# ET-TOP.net
KiCad netlist of a schematic drawn in Altium Designer
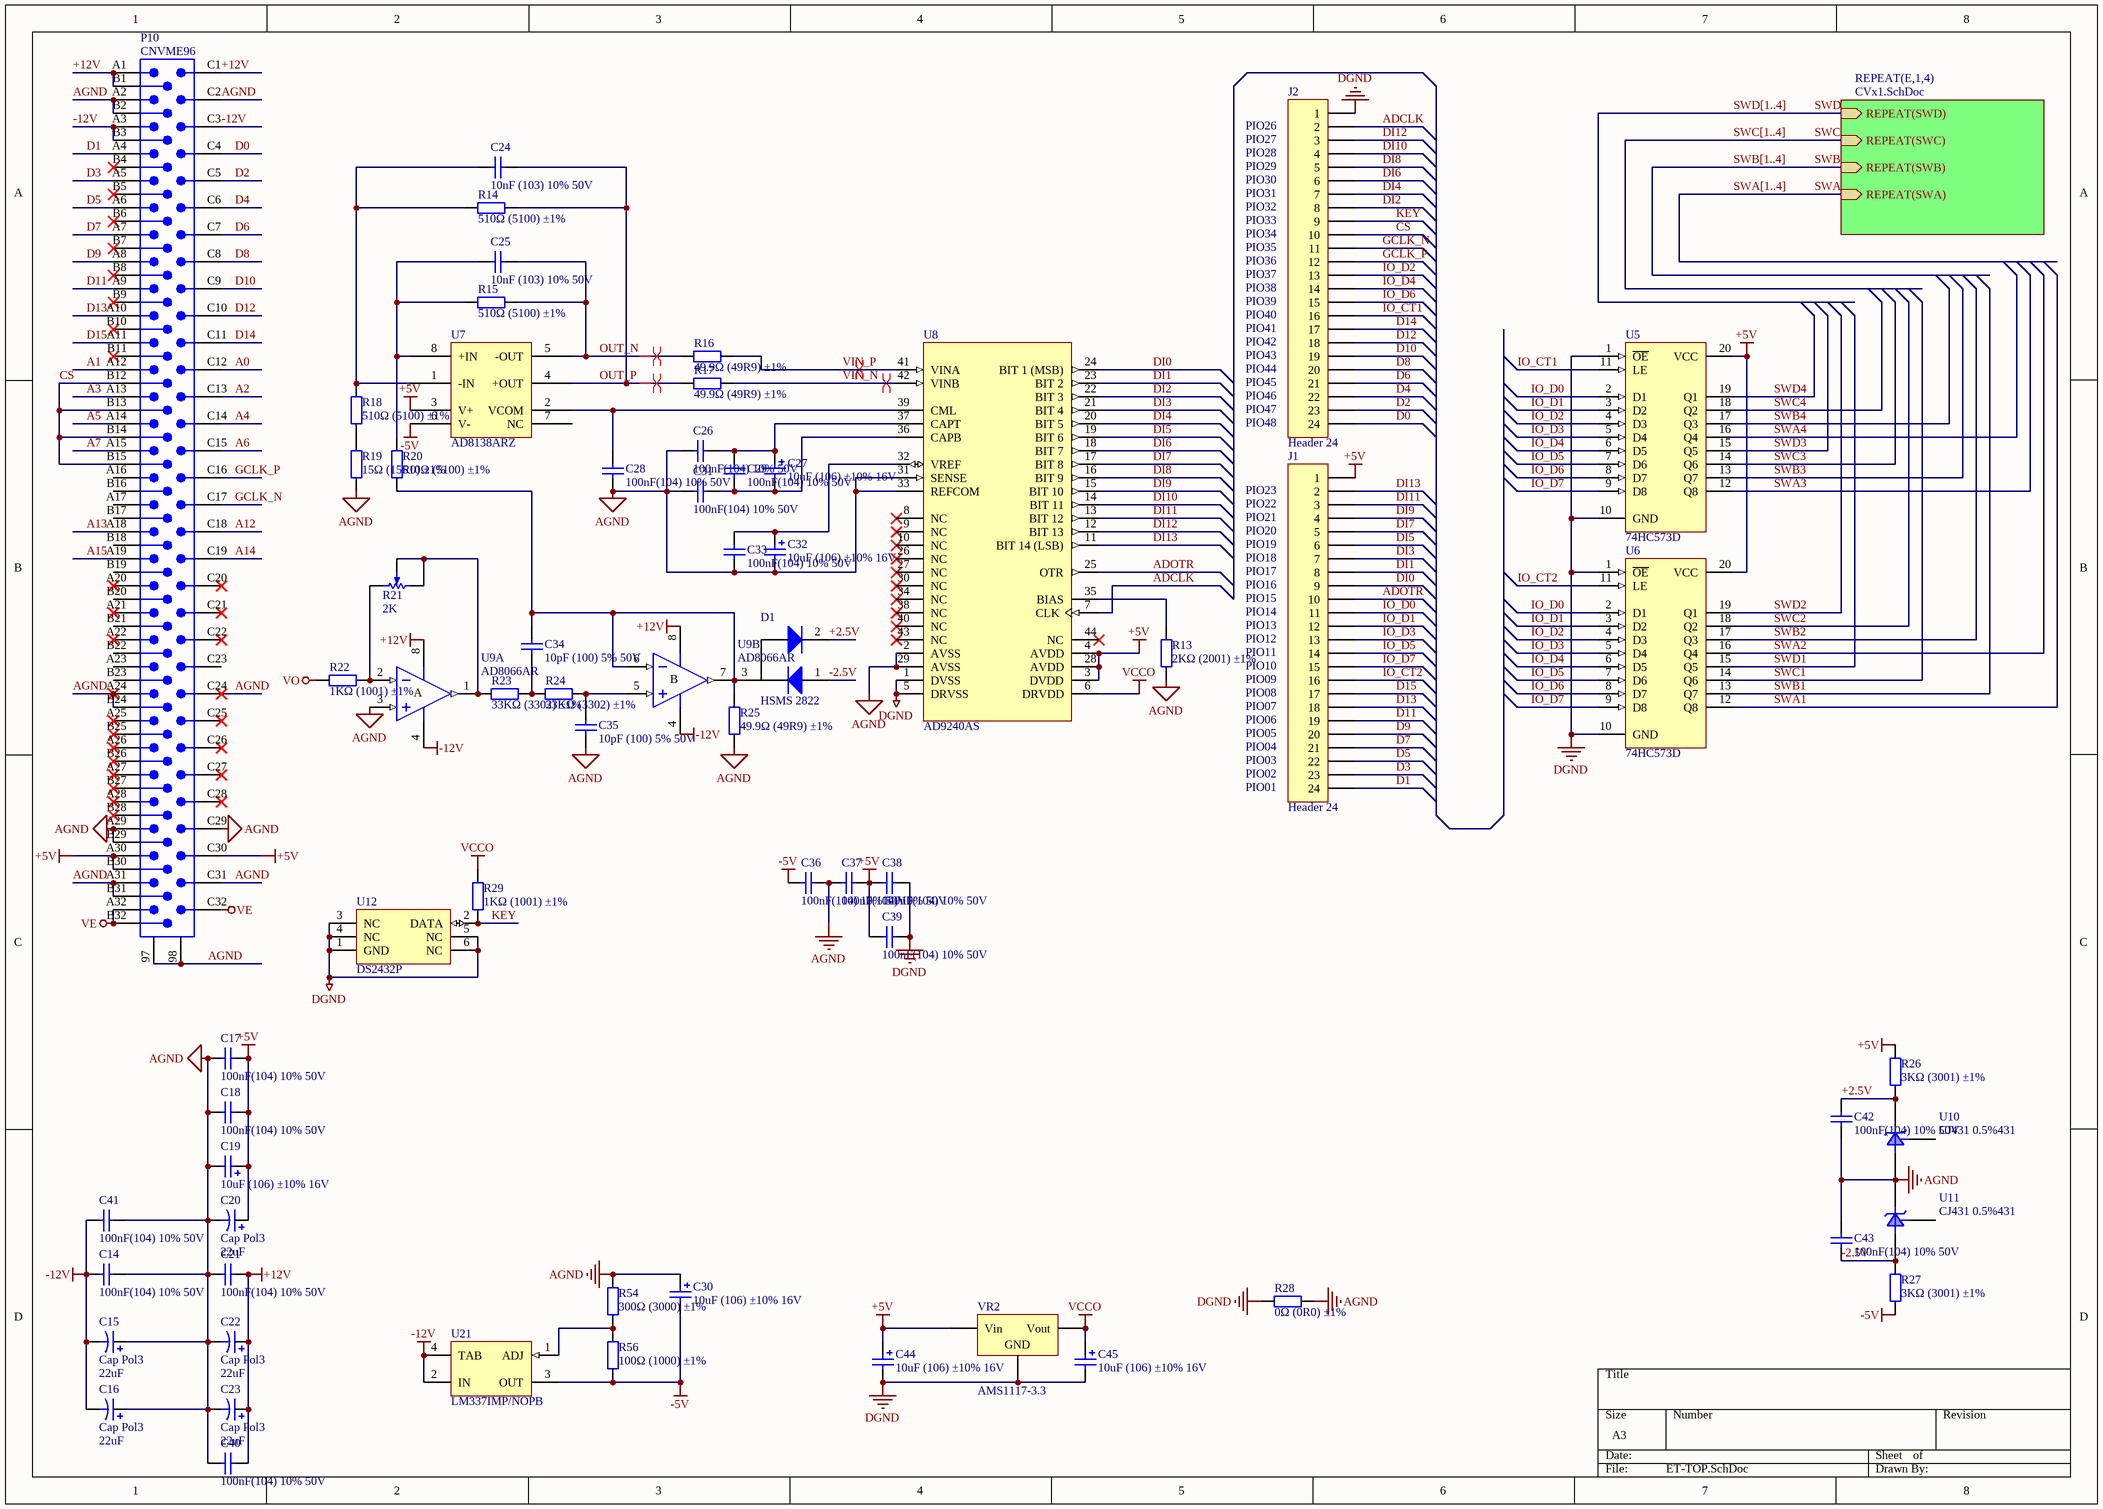
[diagram p0: ET-TOP.SchDoc]

(export (version "E")
  (design (tool "Eeschema 10.0.6"))
  (components
    (comp (ref "C14")
      (value "100nF(104) 10% 50V")
      (footprint "LC-0805_C")
      (description "贴片电容")
      (libsource (lib "Miscellaneous Devices LC") (part "0805 100nF(104) 10% 50V"))
    )
    (comp (ref "C15")
      (value "Cap Pol3")
      (footprint "C2225")
      (description "Polarized Capacitor (Surface Mount)")
      (fields (field (name "ALTIUM_VALUE") "22uF") (field (name "PUBLISHER") "Altium Limited"))
      (libsource (lib "Miscellaneous Devices") (part "Cap Pol3"))
    )
    (comp (ref "C16")
      (value "Cap Pol3")
      (footprint "C2225")
      (description "Polarized Capacitor (Surface Mount)")
      (fields (field (name "ALTIUM_VALUE") "22uF") (field (name "PUBLISHER") "Altium Limited"))
      (libsource (lib "Miscellaneous Devices") (part "Cap Pol3"))
    )
    (comp (ref "C17")
      (value "100nF(104) 10% 50V")
      (footprint "LC-0805_C")
      (description "贴片电容")
      (libsource (lib "Miscellaneous Devices LC") (part "0805 100nF(104) 10% 50V"))
    )
    (comp (ref "C18")
      (value "100nF(104) 10% 50V")
      (footprint "LC-0805_C")
      (description "贴片电容")
      (libsource (lib "Miscellaneous Devices LC") (part "0805 100nF(104) 10% 50V"))
    )
    (comp (ref "C19")
      (value "10uF (106) ±10% 16V")
      (footprint "LC-CASE-A_3216")
      (description "钽电容")
      (libsource (lib "Miscellaneous Devices LC") (part "3216 10uF (106) 10% 16V"))
    )
    (comp (ref "C20")
      (value "Cap Pol3")
      (footprint "C2225")
      (description "Polarized Capacitor (Surface Mount)")
      (fields (field (name "ALTIUM_VALUE") "22uF") (field (name "PUBLISHER") "Altium Limited"))
      (libsource (lib "Miscellaneous Devices") (part "Cap Pol3"))
    )
    (comp (ref "C21")
      (value "100nF(104) 10% 50V")
      (footprint "LC-0805_C")
      (description "贴片电容")
      (libsource (lib "Miscellaneous Devices LC") (part "0805 100nF(104) 10% 50V"))
    )
    (comp (ref "C22")
      (value "Cap Pol3")
      (footprint "C2225")
      (description "Polarized Capacitor (Surface Mount)")
      (fields (field (name "ALTIUM_VALUE") "22uF") (field (name "PUBLISHER") "Altium Limited"))
      (libsource (lib "Miscellaneous Devices") (part "Cap Pol3"))
    )
    (comp (ref "C23")
      (value "Cap Pol3")
      (footprint "C2225")
      (description "Polarized Capacitor (Surface Mount)")
      (fields (field (name "ALTIUM_VALUE") "22uF") (field (name "PUBLISHER") "Altium Limited"))
      (libsource (lib "Miscellaneous Devices") (part "Cap Pol3"))
    )
    (comp (ref "C24")
      (value "10nF (103) 10% 50V")
      (footprint "LC-0805_C")
      (description "贴片电容")
      (libsource (lib "Miscellaneous Devices LC") (part "0805 10nF (103) 10% 50V"))
    )
    (comp (ref "C25")
      (value "10nF (103) 10% 50V")
      (footprint "LC-0805_C")
      (description "贴片电容")
      (libsource (lib "Miscellaneous Devices LC") (part "0805 10nF (103) 10% 50V"))
    )
    (comp (ref "C26")
      (value "100nF(104) 10% 50V")
      (footprint "LC-0805_C")
      (description "贴片电容")
      (libsource (lib "Miscellaneous Devices LC") (part "0805 100nF(104) 10% 50V"))
    )
    (comp (ref "C27")
      (value "10uF (106) ±10% 16V")
      (footprint "LC-CASE-A_3216")
      (description "钽电容")
      (libsource (lib "Miscellaneous Devices LC") (part "3216 10uF (106) 10% 16V"))
    )
    (comp (ref "C28")
      (value "100nF(104) 10% 50V")
      (footprint "LC-0805_C")
      (description "贴片电容")
      (libsource (lib "Miscellaneous Devices LC") (part "0805 100nF(104) 10% 50V"))
    )
    (comp (ref "C29")
      (value "100nF(104) 10% 50V")
      (footprint "LC-0805_C")
      (description "贴片电容")
      (libsource (lib "Miscellaneous Devices LC") (part "0805 100nF(104) 10% 50V"))
    )
    (comp (ref "C30")
      (value "10uF (106) ±10% 16V")
      (footprint "LC-CASE-A_3216")
      (description "钽电容")
      (libsource (lib "Miscellaneous Devices LC") (part "3216 10uF (106) 10% 16V"))
    )
    (comp (ref "C31")
      (value "100nF(104) 10% 50V")
      (footprint "LC-0805_C")
      (description "贴片电容")
      (libsource (lib "Miscellaneous Devices LC") (part "0805 100nF(104) 10% 50V"))
    )
    (comp (ref "C32")
      (value "10uF (106) ±10% 16V")
      (footprint "LC-CASE-A_3216")
      (description "钽电容")
      (libsource (lib "Miscellaneous Devices LC") (part "3216 10uF (106) 10% 16V"))
    )
    (comp (ref "C33")
      (value "100nF(104) 10% 50V")
      (footprint "LC-0805_C")
      (description "贴片电容")
      (libsource (lib "Miscellaneous Devices LC") (part "0805 100nF(104) 10% 50V"))
    )
    (comp (ref "C34")
      (value "10pF (100) 5% 50V")
      (footprint "LC-0805_C")
      (description "贴片电容")
      (libsource (lib "Miscellaneous Devices LC") (part "0805 10pF (100) 5% 50V"))
    )
    (comp (ref "C35")
      (value "10pF (100) 5% 50V")
      (footprint "LC-0805_C")
      (description "贴片电容")
      (libsource (lib "Miscellaneous Devices LC") (part "0805 10pF (100) 5% 50V"))
    )
    (comp (ref "C36")
      (value "100nF(104) 10% 50V")
      (footprint "LC-0805_C")
      (description "贴片电容")
      (libsource (lib "Miscellaneous Devices LC") (part "0805 100nF(104) 10% 50V"))
    )
    (comp (ref "C37")
      (value "100nF(104) 10% 50V")
      (footprint "LC-0805_C")
      (description "贴片电容")
      (libsource (lib "Miscellaneous Devices LC") (part "0805 100nF(104) 10% 50V"))
    )
    (comp (ref "C38")
      (value "100nF(104) 10% 50V")
      (footprint "LC-0805_C")
      (description "贴片电容")
      (libsource (lib "Miscellaneous Devices LC") (part "0805 100nF(104) 10% 50V"))
    )
    (comp (ref "C39")
      (value "100nF(104) 10% 50V")
      (footprint "LC-0805_C")
      (description "贴片电容")
      (libsource (lib "Miscellaneous Devices LC") (part "0805 100nF(104) 10% 50V"))
    )
    (comp (ref "C40")
      (value "100nF(104) 10% 50V")
      (footprint "LC-0805_C")
      (description "贴片电容")
      (libsource (lib "Miscellaneous Devices LC") (part "0805 100nF(104) 10% 50V"))
    )
    (comp (ref "C41")
      (value "100nF(104) 10% 50V")
      (footprint "LC-0805_C")
      (description "贴片电容")
      (libsource (lib "Miscellaneous Devices LC") (part "0805 100nF(104) 10% 50V"))
    )
    (comp (ref "C42")
      (value "100nF(104) 10% 50V")
      (footprint "LC-0805_C")
      (description "贴片电容")
      (libsource (lib "Miscellaneous Devices LC") (part "0805 100nF(104) 10% 50V"))
    )
    (comp (ref "C43")
      (value "100nF(104) 10% 50V")
      (footprint "LC-0805_C")
      (description "贴片电容")
      (libsource (lib "Miscellaneous Devices LC") (part "0805 100nF(104) 10% 50V"))
    )
    (comp (ref "C44")
      (value "10uF (106) ±10% 16V")
      (footprint "LC-CASE-A_3216")
      (description "钽电容")
      (libsource (lib "Miscellaneous Devices LC") (part "3216 10uF (106) 10% 16V"))
    )
    (comp (ref "C45")
      (value "10uF (106) ±10% 16V")
      (footprint "LC-CASE-A_3216")
      (description "钽电容")
      (libsource (lib "Miscellaneous Devices LC") (part "3216 10uF (106) 10% 16V"))
    )
    (comp (ref "D1")
      (value "HSMS 2822")
      (footprint "LC-SOT-23(SOT-23-3)")
      (description "开关二极管")
      (libsource (lib "Miscellaneous Devices LC") (part "SOT-23 BAV99 A7W"))
    )
    (comp (ref "J1")
      (value "Header 24")
      (footprint "HDR1X24")
      (description "Header, 24-Pin")
      (fields (field (name "PUBLISHER") "Altium Limited"))
      (libsource (lib "Miscellaneous Connectors") (part "Header 24"))
    )
    (comp (ref "J2")
      (value "Header 24")
      (footprint "HDR1X24")
      (description "Header, 24-Pin")
      (fields (field (name "PUBLISHER") "Altium Limited"))
      (libsource (lib "Miscellaneous Connectors") (part "Header 24"))
    )
    (comp (ref "P10")
      (value "CNVME96")
      (footprint "CNVME96")
      (description "96-Pin Connector (3x32 2.54mm grid)")
      (libsource (lib "*") (part "CNVME96"))
    )
    (comp (ref "R13")
      (value "2KΩ (2001) ±1%")
      (footprint "LC-0805_R")
      (description "贴片电阻")
      (libsource (lib "Miscellaneous Devices LC") (part "0805 2KΩ (2001) 1%"))
    )
    (comp (ref "R14")
      (value "510Ω (5100) ±1%")
      (footprint "LC-0805_R")
      (description "贴片电阻")
      (libsource (lib "Miscellaneous Devices LC") (part "0805 510Ω (5100) 1%"))
    )
    (comp (ref "R15")
      (value "510Ω (5100) ±1%")
      (footprint "LC-0805_R")
      (description "贴片电阻")
      (libsource (lib "Miscellaneous Devices LC") (part "0805 510Ω (5100) 1%"))
    )
    (comp (ref "R16")
      (value "49.9Ω (49R9) ±1%")
      (footprint "LC-0805_R")
      (description "贴片电阻")
      (libsource (lib "") (part "0805 49.9Ω (49R9) 1%_1"))
    )
    (comp (ref "R17")
      (value "49.9Ω (49R9) ±1%")
      (footprint "LC-0805_R")
      (description "贴片电阻")
      (libsource (lib "") (part "0805 49.9Ω (49R9) 1%_1"))
    )
    (comp (ref "R18")
      (value "510Ω (5100) ±1%")
      (footprint "LC-0805_R")
      (description "贴片电阻")
      (libsource (lib "") (part "0805 510Ω (5100) 1%_1"))
    )
    (comp (ref "R19")
      (value "15Ω (15R0) ±1%")
      (footprint "LC-0805_R")
      (description "贴片电阻")
      (libsource (lib "Miscellaneous Devices LC") (part "0805 15Ω (15R0) 1%"))
    )
    (comp (ref "R20")
      (value "510Ω (5100) ±1%")
      (footprint "LC-0805_R")
      (description "贴片电阻")
      (libsource (lib "") (part "0805 510Ω (5100) 1%_1"))
    )
    (comp (ref "R21")
      (value "2K")
      (footprint "POT4MM-2")
      (description "Square Trimming Potentiometer")
      (fields (field (name "PUBLISHER") "Altium Limited"))
      (libsource (lib "Miscellaneous Devices") (part "RPot SM"))
    )
    (comp (ref "R22")
      (value "1KΩ (1001) ±1%")
      (footprint "LC-0805_R")
      (description "贴片电阻")
      (libsource (lib "Miscellaneous Devices LC") (part "0805 1KΩ (1001) 1%"))
    )
    (comp (ref "R23")
      (value "33KΩ (3302) ±1%")
      (footprint "LC-0805_R")
      (description "贴片电阻")
      (libsource (lib "Miscellaneous Devices LC") (part "0805 33KΩ (3302) 1%"))
    )
    (comp (ref "R24")
      (value "33KΩ (3302) ±1%")
      (footprint "LC-0805_R")
      (description "贴片电阻")
      (libsource (lib "Miscellaneous Devices LC") (part "0805 33KΩ (3302) 1%"))
    )
    (comp (ref "R25")
      (value "49.9Ω (49R9) ±1%")
      (footprint "LC-0805_R")
      (description "贴片电阻")
      (libsource (lib "Miscellaneous Devices LC") (part "0805 49.9Ω (49R9) 1%"))
    )
    (comp (ref "R26")
      (value "3KΩ (3001) ±1%")
      (footprint "LC-0805_R")
      (description "贴片电阻")
      (libsource (lib "Miscellaneous Devices LC") (part "0805 3KΩ (3001) 1%"))
    )
    (comp (ref "R27")
      (value "3KΩ (3001) ±1%")
      (footprint "LC-0805_R")
      (description "贴片电阻")
      (libsource (lib "Miscellaneous Devices LC") (part "0805 3KΩ (3001) 1%"))
    )
    (comp (ref "R28")
      (value "0Ω (0R0) ±1%")
      (footprint "LC-0805_R")
      (description "贴片电阻")
      (libsource (lib "Miscellaneous Devices LC") (part "0805 0Ω (0R0) 1%"))
    )
    (comp (ref "R29")
      (value "1KΩ (1001) ±1%")
      (footprint "LC-0805_R")
      (description "贴片电阻")
      (libsource (lib "") (part "0805 1KΩ (1001) 1%_1"))
    )
    (comp (ref "R54")
      (value "300Ω (3000) ±1%")
      (footprint "LC-0805_R")
      (description "贴片电阻")
      (libsource (lib "Miscellaneous Devices LC") (part "0805 300Ω (3000) 1%"))
    )
    (comp (ref "R56")
      (value "100Ω (1000) ±1%")
      (footprint "LC-0805_R")
      (description "贴片电阻")
      (libsource (lib "Miscellaneous Devices LC") (part "0805 100Ω (1000) 1%"))
    )
    (comp (ref "U5")
      (value "74HC573D")
      (footprint "LC-SOIC-20_300mil")
      (description "74系列逻辑芯片")
      (libsource (lib "Miscellaneous Devices LC") (part "74HC573D"))
    )
    (comp (ref "U6")
      (value "74HC573D")
      (footprint "LC-SOIC-20_300mil")
      (description "74系列逻辑芯片")
      (libsource (lib "Miscellaneous Devices LC") (part "74HC573D"))
    )
    (comp (ref "U7") (value "AD8138ARZ") (footprint "SO-8_N") (libsource (lib "AD8138") (part "AD8138ARZ")))
    (comp (ref "U8")
      (value "AD9240AS")
      (footprint "S-44-MQFP_N")
      (description "Complete 14-Bit, 10 MSPS Monolithic A/D Converter, 44-Pin MQFP, Industrial")
      (fields (field (name "PUBLISHER") "Altium Limited"))
      (libsource (lib "AD Converter Analog to Digital") (part "AD9240AS"))
    )
    (comp (ref "U9")
      (value "AD8066AR")
      (footprint "mini-ET:SO-8_N")
      (description "Low Cost, 300MHz Voltage Feedback Amplifier")
      (fields (field (name "PUBLISHER") "Altium Limited"))
      (libsource (lib "AD Operational Amplifier") (part "AD8056AR"))
    )
    (comp (ref "U10")
      (value "CJ431 0.5%431")
      (footprint "LC-SOT-23(SOT-23-3)")
      (description "电压基准")
      (libsource (lib "Miscellaneous Devices LC") (part "CJ431 0.5%431"))
    )
    (comp (ref "U11")
      (value "CJ431 0.5%431")
      (footprint "LC-SOT-23(SOT-23-3)")
      (description "电压基准")
      (libsource (lib "Miscellaneous Devices LC") (part "CJ431 0.5%431"))
    )
    (comp (ref "U12")
      (value "DS2432P")
      (footprint "TSOC6")
      (description "256-Bit 1-Wire EEPROM")
      (fields (field (name "PUBLISHER") "Altium Limited"))
      (libsource (lib "Dallas Memory EEPROM") (part "DS2430AP"))
    )
    (comp (ref "U21")
      (value "LM337IMP/NOPB")
      (footprint "MP04A_N")
      (description "3-Terminal Adjustable Negative Regulator, 4-pin SOT-223, Pb-Free")
      (fields
        (field (name "MANUFACTURER") "National Semiconductor")
        (field (name "PUBLISHER") "Altium Limited")
      )
      (libsource (lib "NSC LDO") (part "LM337IMP/NOPB"))
    )
    (comp (ref "VR2")
      (value "AMS1117-3.3")
      (footprint "LC-SOT-223")
      (description "低压差线性稳压(LDO)")
      (libsource (lib "Miscellaneous Devices LC") (part "SOT-223 AMS1117-3.3"))
    )
  )
  (nets
    (net (code "1") (name "+5V") (class "Default")
      (node (ref "C17") (pin "2") (pinfunction "2_2") (pintype "passive"))
      (node (ref "C18") (pin "2") (pinfunction "2_2") (pintype "passive"))
      (node (ref "C19") (pin "1") (pinfunction "1_1") (pintype "passive"))
      (node (ref "C20") (pin "1") (pinfunction "1_1") (pintype "passive"))
      (node (ref "C37") (pin "1") (pinfunction "1_1") (pintype "passive"))
      (node (ref "C38") (pin "2") (pinfunction "2_2") (pintype "passive"))
      (node (ref "C39") (pin "2") (pinfunction "2_2") (pintype "passive"))
      (node (ref "C44") (pin "1") (pinfunction "1_1") (pintype "passive"))
      (node (ref "J1") (pin "1") (pinfunction "1_1") (pintype "passive"))
      (node (ref "P10") (pin "A30") (pinfunction "A30_A30") (pintype "passive"))
      (node (ref "P10") (pin "B30") (pinfunction "B30_B30") (pintype "passive"))
      (node (ref "P10") (pin "C30") (pinfunction "C30_C30") (pintype "passive"))
      (node (ref "R26") (pin "2") (pinfunction "2_2") (pintype "passive"))
      (node (ref "U5") (pin "20") (pinfunction "VCC_20") (pintype "power_in"))
      (node (ref "U6") (pin "20") (pinfunction "VCC_20") (pintype "power_in"))
      (node (ref "U7") (pin "3") (pinfunction "V+_3") (pintype "passive"))
      (node (ref "U8") (pin "28") (pinfunction "AVDD_28") (pintype "power_in"))
      (node (ref "U8") (pin "3") (pinfunction "DVDD_3") (pintype "power_in"))
      (node (ref "U8") (pin "4") (pinfunction "AVDD_4") (pintype "power_in"))
      (node (ref "VR2") (pin "3") (pinfunction "Vin_3") (pintype "passive"))
    )
    (net (code "2") (name "+12V") (class "Default")
      (node (ref "C21") (pin "2") (pinfunction "2_2") (pintype "passive"))
      (node (ref "C22") (pin "1") (pinfunction "1_1") (pintype "passive"))
      (node (ref "C23") (pin "1") (pinfunction "1_1") (pintype "passive"))
      (node (ref "C40") (pin "1") (pinfunction "1_1") (pintype "passive"))
      (node (ref "P10") (pin "A1") (pinfunction "A1_A1") (pintype "passive"))
      (node (ref "P10") (pin "B1") (pinfunction "B1_B1") (pintype "passive"))
      (node (ref "P10") (pin "C1") (pinfunction "C1_C1") (pintype "passive"))
      (node (ref "U9") (pin "8") (pinfunction "V+_8") (pintype "power_in"))
    )
    (net (code "3") (name "-5V") (class "Default")
      (node (ref "C30") (pin "2") (pinfunction "2_2") (pintype "passive"))
      (node (ref "C36") (pin "2") (pinfunction "2_2") (pintype "passive"))
      (node (ref "R27") (pin "1") (pinfunction "1_1") (pintype "passive"))
      (node (ref "R56") (pin "1") (pinfunction "1_1") (pintype "passive"))
      (node (ref "U21") (pin "3") (pinfunction "OUT_3") (pintype "power_in"))
      (node (ref "U7") (pin "6") (pinfunction "V-_6") (pintype "passive"))
    )
    (net (code "4") (name "-12V") (class "Default")
      (node (ref "C14") (pin "1") (pinfunction "1_1") (pintype "passive"))
      (node (ref "C15") (pin "2") (pinfunction "2_2") (pintype "passive"))
      (node (ref "C16") (pin "2") (pinfunction "2_2") (pintype "passive"))
      (node (ref "C41") (pin "2") (pinfunction "2_2") (pintype "passive"))
      (node (ref "P10") (pin "A3") (pinfunction "A3_A3") (pintype "passive"))
      (node (ref "P10") (pin "B3") (pinfunction "B3_B3") (pintype "passive"))
      (node (ref "P10") (pin "C3") (pinfunction "C3_C3") (pintype "passive"))
      (node (ref "U21") (pin "2") (pinfunction "IN_2") (pintype "power_in"))
      (node (ref "U21") (pin "4") (pinfunction "TAB_4") (pintype "power_in"))
      (node (ref "U9") (pin "4") (pinfunction "V-_4") (pintype "power_in"))
    )
    (net (code "5") (name "/+2.5V") (class "Default")
      (node (ref "C42") (pin "1") (pinfunction "1_1") (pintype "passive"))
      (node (ref "D1") (pin "2") (pinfunction "A_2") (pintype "passive"))
      (node (ref "R26") (pin "1") (pinfunction "1_1") (pintype "passive"))
      (node (ref "U10") (pin "2") (pinfunction "K_2") (pintype "passive"))
    )
    (net (code "6") (name "/-2.5V") (class "Default")
      (node (ref "C43") (pin "2") (pinfunction "2_2") (pintype "passive"))
      (node (ref "D1") (pin "1") (pinfunction "A_1") (pintype "passive"))
      (node (ref "R27") (pin "2") (pinfunction "2_2") (pintype "passive"))
      (node (ref "U11") (pin "3") (pinfunction "A_3") (pintype "passive"))
    )
    (net (code "7") (name "/A0") (class "Default")
      (node (ref "P10") (pin "C12") (pinfunction "C12_C12") (pintype "passive"))
    )
    (net (code "8") (name "/A1") (class "Default")
      (node (ref "P10") (pin "A12") (pinfunction "A12_A12") (pintype "passive"))
    )
    (net (code "9") (name "/A2") (class "Default")
      (node (ref "P10") (pin "C13") (pinfunction "C13_C13") (pintype "passive"))
    )
    (net (code "10") (name "/A3") (class "Default")
      (node (ref "P10") (pin "A13") (pinfunction "A13_A13") (pintype "passive"))
    )
    (net (code "11") (name "/A4") (class "Default")
      (node (ref "P10") (pin "C14") (pinfunction "C14_C14") (pintype "passive"))
    )
    (net (code "12") (name "/A5") (class "Default")
      (node (ref "P10") (pin "A14") (pinfunction "A14_A14") (pintype "passive"))
    )
    (net (code "13") (name "/A6") (class "Default")
      (node (ref "P10") (pin "C15") (pinfunction "C15_C15") (pintype "passive"))
    )
    (net (code "14") (name "/A7") (class "Default")
      (node (ref "P10") (pin "A15") (pinfunction "A15_A15") (pintype "passive"))
    )
    (net (code "15") (name "/A12") (class "Default")
      (node (ref "P10") (pin "C18") (pinfunction "C18_C18") (pintype "passive"))
    )
    (net (code "16") (name "/A13") (class "Default")
      (node (ref "P10") (pin "A18") (pinfunction "A18_A18") (pintype "passive"))
    )
    (net (code "17") (name "/A14") (class "Default")
      (node (ref "P10") (pin "C19") (pinfunction "C19_C19") (pintype "passive"))
    )
    (net (code "18") (name "/A15") (class "Default")
      (node (ref "P10") (pin "A19") (pinfunction "A19_A19") (pintype "passive"))
    )
    (net (code "19") (name "/ADCLK") (class "Default")
      (node (ref "J2") (pin "2") (pinfunction "2_2") (pintype "passive"))
      (node (ref "U8") (pin "7") (pinfunction "CLK_7") (pintype "input"))
    )
    (net (code "20") (name "/ADOTR") (class "Default")
      (node (ref "J1") (pin "10") (pinfunction "10_10") (pintype "passive"))
      (node (ref "U8") (pin "25") (pinfunction "OTR_25") (pintype "output"))
    )
    (net (code "21") (name "/CS") (class "Default")
      (node (ref "J2") (pin "10") (pinfunction "10_10") (pintype "passive"))
      (node (ref "P10") (pin "B12") (pinfunction "B12_B12") (pintype "passive"))
      (node (ref "P10") (pin "B13") (pinfunction "B13_B13") (pintype "passive"))
      (node (ref "P10") (pin "B14") (pinfunction "B14_B14") (pintype "passive"))
      (node (ref "P10") (pin "B15") (pinfunction "B15_B15") (pintype "passive"))
    )
    (net (code "22") (name "/D0") (class "Default")
      (node (ref "J2") (pin "24") (pinfunction "24_24") (pintype "passive"))
      (node (ref "P10") (pin "C4") (pinfunction "C4_C4") (pintype "passive"))
    )
    (net (code "23") (name "/D1") (class "Default")
      (node (ref "J1") (pin "24") (pinfunction "24_24") (pintype "passive"))
      (node (ref "P10") (pin "A4") (pinfunction "A4_A4") (pintype "passive"))
    )
    (net (code "24") (name "/D2") (class "Default")
      (node (ref "J2") (pin "23") (pinfunction "23_23") (pintype "passive"))
      (node (ref "P10") (pin "C5") (pinfunction "C5_C5") (pintype "passive"))
    )
    (net (code "25") (name "/D3") (class "Default")
      (node (ref "J1") (pin "23") (pinfunction "23_23") (pintype "passive"))
      (node (ref "P10") (pin "A5") (pinfunction "A5_A5") (pintype "passive"))
    )
    (net (code "26") (name "/D4") (class "Default")
      (node (ref "J2") (pin "22") (pinfunction "22_22") (pintype "passive"))
      (node (ref "P10") (pin "C6") (pinfunction "C6_C6") (pintype "passive"))
    )
    (net (code "27") (name "/D5") (class "Default")
      (node (ref "J1") (pin "22") (pinfunction "22_22") (pintype "passive"))
      (node (ref "P10") (pin "A6") (pinfunction "A6_A6") (pintype "passive"))
    )
    (net (code "28") (name "/D6") (class "Default")
      (node (ref "J2") (pin "21") (pinfunction "21_21") (pintype "passive"))
      (node (ref "P10") (pin "C7") (pinfunction "C7_C7") (pintype "passive"))
    )
    (net (code "29") (name "/D7") (class "Default")
      (node (ref "J1") (pin "21") (pinfunction "21_21") (pintype "passive"))
      (node (ref "P10") (pin "A7") (pinfunction "A7_A7") (pintype "passive"))
    )
    (net (code "30") (name "/D8") (class "Default")
      (node (ref "J2") (pin "20") (pinfunction "20_20") (pintype "passive"))
      (node (ref "P10") (pin "C8") (pinfunction "C8_C8") (pintype "passive"))
    )
    (net (code "31") (name "/D9") (class "Default")
      (node (ref "J1") (pin "20") (pinfunction "20_20") (pintype "passive"))
      (node (ref "P10") (pin "A8") (pinfunction "A8_A8") (pintype "passive"))
    )
    (net (code "32") (name "/D10") (class "Default")
      (node (ref "J2") (pin "19") (pinfunction "19_19") (pintype "passive"))
      (node (ref "P10") (pin "C9") (pinfunction "C9_C9") (pintype "passive"))
    )
    (net (code "33") (name "/D11") (class "Default")
      (node (ref "J1") (pin "19") (pinfunction "19_19") (pintype "passive"))
      (node (ref "P10") (pin "A9") (pinfunction "A9_A9") (pintype "passive"))
    )
    (net (code "34") (name "/D12") (class "Default")
      (node (ref "J2") (pin "18") (pinfunction "18_18") (pintype "passive"))
      (node (ref "P10") (pin "C10") (pinfunction "C10_C10") (pintype "passive"))
    )
    (net (code "35") (name "/D13") (class "Default")
      (node (ref "J1") (pin "18") (pinfunction "18_18") (pintype "passive"))
      (node (ref "P10") (pin "A10") (pinfunction "A10_A10") (pintype "passive"))
    )
    (net (code "36") (name "/D14") (class "Default")
      (node (ref "J2") (pin "17") (pinfunction "17_17") (pintype "passive"))
      (node (ref "P10") (pin "C11") (pinfunction "C11_C11") (pintype "passive"))
    )
    (net (code "37") (name "/D15") (class "Default")
      (node (ref "J1") (pin "17") (pinfunction "17_17") (pintype "passive"))
      (node (ref "P10") (pin "A11") (pinfunction "A11_A11") (pintype "passive"))
    )
    (net (code "38") (name "/DI0") (class "Default")
      (node (ref "J1") (pin "9") (pinfunction "9_9") (pintype "passive"))
      (node (ref "U8") (pin "24") (pinfunction "BIT_1_(MSB)_24") (pintype "output"))
    )
    (net (code "39") (name "/DI1") (class "Default")
      (node (ref "J1") (pin "8") (pinfunction "8_8") (pintype "passive"))
      (node (ref "U8") (pin "23") (pinfunction "BIT_2_23") (pintype "output"))
    )
    (net (code "40") (name "/DI2") (class "Default")
      (node (ref "J2") (pin "8") (pinfunction "8_8") (pintype "passive"))
      (node (ref "U8") (pin "22") (pinfunction "BIT_3_22") (pintype "output"))
    )
    (net (code "41") (name "/DI3") (class "Default")
      (node (ref "J1") (pin "7") (pinfunction "7_7") (pintype "passive"))
      (node (ref "U8") (pin "21") (pinfunction "BIT_4_21") (pintype "output"))
    )
    (net (code "42") (name "/DI4") (class "Default")
      (node (ref "J2") (pin "7") (pinfunction "7_7") (pintype "passive"))
      (node (ref "U8") (pin "20") (pinfunction "BIT_5_20") (pintype "output"))
    )
    (net (code "43") (name "/DI5") (class "Default")
      (node (ref "J1") (pin "6") (pinfunction "6_6") (pintype "passive"))
      (node (ref "U8") (pin "19") (pinfunction "BIT_6_19") (pintype "output"))
    )
    (net (code "44") (name "/DI6") (class "Default")
      (node (ref "J2") (pin "6") (pinfunction "6_6") (pintype "passive"))
      (node (ref "U8") (pin "18") (pinfunction "BIT_7_18") (pintype "output"))
    )
    (net (code "45") (name "/DI7") (class "Default")
      (node (ref "J1") (pin "5") (pinfunction "5_5") (pintype "passive"))
      (node (ref "U8") (pin "17") (pinfunction "BIT_8_17") (pintype "output"))
    )
    (net (code "46") (name "/DI8") (class "Default")
      (node (ref "J2") (pin "5") (pinfunction "5_5") (pintype "passive"))
      (node (ref "U8") (pin "16") (pinfunction "BIT_9_16") (pintype "output"))
    )
    (net (code "47") (name "/DI9") (class "Default")
      (node (ref "J1") (pin "4") (pinfunction "4_4") (pintype "passive"))
      (node (ref "U8") (pin "15") (pinfunction "BIT_10_15") (pintype "output"))
    )
    (net (code "48") (name "/DI10") (class "Default")
      (node (ref "J2") (pin "4") (pinfunction "4_4") (pintype "passive"))
      (node (ref "U8") (pin "14") (pinfunction "BIT_11_14") (pintype "output"))
    )
    (net (code "49") (name "/DI11") (class "Default")
      (node (ref "J1") (pin "3") (pinfunction "3_3") (pintype "passive"))
      (node (ref "U8") (pin "13") (pinfunction "BIT_12_13") (pintype "output"))
    )
    (net (code "50") (name "/DI12") (class "Default")
      (node (ref "J2") (pin "3") (pinfunction "3_3") (pintype "passive"))
      (node (ref "U8") (pin "12") (pinfunction "BIT_13_12") (pintype "output"))
    )
    (net (code "51") (name "/DI13") (class "Default")
      (node (ref "J1") (pin "2") (pinfunction "2_2") (pintype "passive"))
      (node (ref "U8") (pin "11") (pinfunction "BIT_14_(LSB)_11") (pintype "output"))
    )
    (net (code "52") (name "/GCLK_N") (class "Default")
      (node (ref "J2") (pin "11") (pinfunction "11_11") (pintype "passive"))
      (node (ref "P10") (pin "C17") (pinfunction "C17_C17") (pintype "passive"))
    )
    (net (code "53") (name "/GCLK_P") (class "Default")
      (node (ref "J2") (pin "12") (pinfunction "12_12") (pintype "passive"))
      (node (ref "P10") (pin "C16") (pinfunction "C16_C16") (pintype "passive"))
    )
    (net (code "54") (name "/IO_CT1") (class "Default")
      (node (ref "J2") (pin "16") (pinfunction "16_16") (pintype "passive"))
      (node (ref "U5") (pin "11") (pinfunction "LE_11") (pintype "input"))
    )
    (net (code "55") (name "/IO_CT2") (class "Default")
      (node (ref "J1") (pin "16") (pinfunction "16_16") (pintype "passive"))
      (node (ref "U6") (pin "11") (pinfunction "LE_11") (pintype "input"))
    )
    (net (code "56") (name "/IO_D0") (class "Default")
      (node (ref "J1") (pin "11") (pinfunction "11_11") (pintype "passive"))
      (node (ref "U5") (pin "2") (pinfunction "D1_2") (pintype "input"))
      (node (ref "U6") (pin "2") (pinfunction "D1_2") (pintype "input"))
    )
    (net (code "57") (name "/IO_D1") (class "Default")
      (node (ref "J1") (pin "12") (pinfunction "12_12") (pintype "passive"))
      (node (ref "U5") (pin "3") (pinfunction "D2_3") (pintype "input"))
      (node (ref "U6") (pin "3") (pinfunction "D2_3") (pintype "input"))
    )
    (net (code "58") (name "/IO_D2") (class "Default")
      (node (ref "J2") (pin "13") (pinfunction "13_13") (pintype "passive"))
      (node (ref "U5") (pin "4") (pinfunction "D3_4") (pintype "input"))
      (node (ref "U6") (pin "4") (pinfunction "D3_4") (pintype "input"))
    )
    (net (code "59") (name "/IO_D3") (class "Default")
      (node (ref "J1") (pin "13") (pinfunction "13_13") (pintype "passive"))
      (node (ref "U5") (pin "5") (pinfunction "D4_5") (pintype "input"))
      (node (ref "U6") (pin "5") (pinfunction "D4_5") (pintype "input"))
    )
    (net (code "60") (name "/IO_D4") (class "Default")
      (node (ref "J2") (pin "14") (pinfunction "14_14") (pintype "passive"))
      (node (ref "U5") (pin "6") (pinfunction "D5_6") (pintype "input"))
      (node (ref "U6") (pin "6") (pinfunction "D5_6") (pintype "input"))
    )
    (net (code "61") (name "/IO_D5") (class "Default")
      (node (ref "J1") (pin "14") (pinfunction "14_14") (pintype "passive"))
      (node (ref "U5") (pin "7") (pinfunction "D6_7") (pintype "input"))
      (node (ref "U6") (pin "7") (pinfunction "D6_7") (pintype "input"))
    )
    (net (code "62") (name "/IO_D6") (class "Default")
      (node (ref "J2") (pin "15") (pinfunction "15_15") (pintype "passive"))
      (node (ref "U5") (pin "8") (pinfunction "D7_8") (pintype "input"))
      (node (ref "U6") (pin "8") (pinfunction "D7_8") (pintype "input"))
    )
    (net (code "63") (name "/IO_D7") (class "Default")
      (node (ref "J1") (pin "15") (pinfunction "15_15") (pintype "passive"))
      (node (ref "U5") (pin "9") (pinfunction "D8_9") (pintype "input"))
      (node (ref "U6") (pin "9") (pinfunction "D8_9") (pintype "input"))
    )
    (net (code "64") (name "/KEY") (class "Default")
      (node (ref "J2") (pin "9") (pinfunction "9_9") (pintype "passive"))
      (node (ref "R29") (pin "1") (pinfunction "1_1") (pintype "passive"))
      (node (ref "U12") (pin "2") (pinfunction "DATA_2") (pintype "bidirectional"))
    )
    (net (code "65") (name "/OUT_N") (class "Default")
      (node (ref "C25") (pin "2") (pinfunction "2_2") (pintype "passive"))
      (node (ref "R15") (pin "2") (pinfunction "2_2") (pintype "passive"))
      (node (ref "R16") (pin "1") (pinfunction "1_1") (pintype "passive"))
      (node (ref "U7") (pin "5") (pinfunction "-OUT_5") (pintype "passive"))
    )
    (net (code "66") (name "/OUT_P") (class "Default")
      (node (ref "C24") (pin "2") (pinfunction "2_2") (pintype "passive"))
      (node (ref "R14") (pin "2") (pinfunction "2_2") (pintype "passive"))
      (node (ref "R17") (pin "1") (pinfunction "1_1") (pintype "passive"))
      (node (ref "U7") (pin "4") (pinfunction "+OUT_4") (pintype "passive"))
    )
    (net (code "68") (name "/SWA1") (class "Default")
      (node (ref "U6") (pin "12") (pinfunction "Q8_12") (pintype "tri_state"))
    )
    (net (code "69") (name "/SWA2") (class "Default")
      (node (ref "U6") (pin "16") (pinfunction "Q4_16") (pintype "tri_state"))
    )
    (net (code "70") (name "/SWA3") (class "Default")
      (node (ref "U5") (pin "12") (pinfunction "Q8_12") (pintype "tri_state"))
    )
    (net (code "71") (name "/SWA4") (class "Default")
      (node (ref "U5") (pin "16") (pinfunction "Q4_16") (pintype "tri_state"))
    )
    (net (code "74") (name "/SWB1") (class "Default")
      (node (ref "U6") (pin "13") (pinfunction "Q7_13") (pintype "tri_state"))
    )
    (net (code "75") (name "/SWB2") (class "Default")
      (node (ref "U6") (pin "17") (pinfunction "Q3_17") (pintype "tri_state"))
    )
    (net (code "76") (name "/SWB3") (class "Default")
      (node (ref "U5") (pin "13") (pinfunction "Q7_13") (pintype "tri_state"))
    )
    (net (code "77") (name "/SWB4") (class "Default")
      (node (ref "U5") (pin "17") (pinfunction "Q3_17") (pintype "tri_state"))
    )
    (net (code "80") (name "/SWC1") (class "Default")
      (node (ref "U6") (pin "14") (pinfunction "Q6_14") (pintype "tri_state"))
    )
    (net (code "81") (name "/SWC2") (class "Default")
      (node (ref "U6") (pin "18") (pinfunction "Q2_18") (pintype "tri_state"))
    )
    (net (code "82") (name "/SWC3") (class "Default")
      (node (ref "U5") (pin "14") (pinfunction "Q6_14") (pintype "tri_state"))
    )
    (net (code "83") (name "/SWC4") (class "Default")
      (node (ref "U5") (pin "18") (pinfunction "Q2_18") (pintype "tri_state"))
    )
    (net (code "86") (name "/SWD1") (class "Default")
      (node (ref "U6") (pin "15") (pinfunction "Q5_15") (pintype "tri_state"))
    )
    (net (code "87") (name "/SWD2") (class "Default")
      (node (ref "U6") (pin "19") (pinfunction "Q1_19") (pintype "tri_state"))
    )
    (net (code "88") (name "/SWD3") (class "Default")
      (node (ref "U5") (pin "15") (pinfunction "Q5_15") (pintype "tri_state"))
    )
    (net (code "89") (name "/SWD4") (class "Default")
      (node (ref "U5") (pin "19") (pinfunction "Q1_19") (pintype "tri_state"))
    )
    (net (code "91") (name "/VIN_N") (class "Default")
      (node (ref "R17") (pin "2") (pinfunction "2_2") (pintype "passive"))
      (node (ref "U8") (pin "42") (pinfunction "VINB_42") (pintype "input"))
    )
    (net (code "92") (name "/VIN_P") (class "Default")
      (node (ref "R16") (pin "2") (pinfunction "2_2") (pintype "passive"))
      (node (ref "U8") (pin "41") (pinfunction "VINA_41") (pintype "input"))
    )
    (net (code "93") (name "AGND") (class "Default")
      (node (ref "C14") (pin "2") (pinfunction "2_2") (pintype "passive"))
      (node (ref "C15") (pin "1") (pinfunction "1_1") (pintype "passive"))
      (node (ref "C16") (pin "1") (pinfunction "1_1") (pintype "passive"))
      (node (ref "C17") (pin "1") (pinfunction "1_1") (pintype "passive"))
      (node (ref "C18") (pin "1") (pinfunction "1_1") (pintype "passive"))
      (node (ref "C19") (pin "2") (pinfunction "2_2") (pintype "passive"))
      (node (ref "C20") (pin "2") (pinfunction "2_2") (pintype "passive"))
      (node (ref "C21") (pin "1") (pinfunction "1_1") (pintype "passive"))
      (node (ref "C22") (pin "2") (pinfunction "2_2") (pintype "passive"))
      (node (ref "C23") (pin "2") (pinfunction "2_2") (pintype "passive"))
      (node (ref "C26") (pin "2") (pinfunction "2_2") (pintype "passive"))
      (node (ref "C28") (pin "1") (pinfunction "1_1") (pintype "passive"))
      (node (ref "C30") (pin "1") (pinfunction "1_1") (pintype "passive"))
      (node (ref "C31") (pin "2") (pinfunction "2_2") (pintype "passive"))
      (node (ref "C32") (pin "2") (pinfunction "2_2") (pintype "passive"))
      (node (ref "C33") (pin "1") (pinfunction "1_1") (pintype "passive"))
      (node (ref "C35") (pin "1") (pinfunction "1_1") (pintype "passive"))
      (node (ref "C36") (pin "1") (pinfunction "1_1") (pintype "passive"))
      (node (ref "C37") (pin "2") (pinfunction "2_2") (pintype "passive"))
      (node (ref "C40") (pin "2") (pinfunction "2_2") (pintype "passive"))
      (node (ref "C41") (pin "1") (pinfunction "1_1") (pintype "passive"))
      (node (ref "C42") (pin "2") (pinfunction "2_2") (pintype "passive"))
      (node (ref "C43") (pin "1") (pinfunction "1_1") (pintype "passive"))
      (node (ref "P10") (pin "97") (pinfunction "97_97") (pintype "passive"))
      (node (ref "P10") (pin "98") (pinfunction "98_98") (pintype "passive"))
      (node (ref "P10") (pin "A2") (pinfunction "A2_A2") (pintype "passive"))
      (node (ref "P10") (pin "A24") (pinfunction "A24_A24") (pintype "passive"))
      (node (ref "P10") (pin "A29") (pinfunction "A29_A29") (pintype "passive"))
      (node (ref "P10") (pin "A31") (pinfunction "A31_A31") (pintype "passive"))
      (node (ref "P10") (pin "B2") (pinfunction "B2_B2") (pintype "passive"))
      (node (ref "P10") (pin "B24") (pinfunction "B24_B24") (pintype "passive"))
      (node (ref "P10") (pin "B29") (pinfunction "B29_B29") (pintype "passive"))
      (node (ref "P10") (pin "B31") (pinfunction "B31_B31") (pintype "passive"))
      (node (ref "P10") (pin "C2") (pinfunction "C2_C2") (pintype "passive"))
      (node (ref "P10") (pin "C24") (pinfunction "C24_C24") (pintype "passive"))
      (node (ref "P10") (pin "C29") (pinfunction "C29_C29") (pintype "passive"))
      (node (ref "P10") (pin "C31") (pinfunction "C31_C31") (pintype "passive"))
      (node (ref "R13") (pin "1") (pinfunction "1_1") (pintype "passive"))
      (node (ref "R19") (pin "1") (pinfunction "1_1") (pintype "passive"))
      (node (ref "R25") (pin "1") (pinfunction "1_1") (pintype "passive"))
      (node (ref "R28") (pin "2") (pinfunction "2_2") (pintype "passive"))
      (node (ref "R54") (pin "2") (pinfunction "2_2") (pintype "passive"))
      (node (ref "U10") (pin "3") (pinfunction "A_3") (pintype "passive"))
      (node (ref "U11") (pin "2") (pinfunction "K_2") (pintype "passive"))
      (node (ref "U8") (pin "2") (pinfunction "AVSS_2") (pintype "power_in"))
      (node (ref "U8") (pin "29") (pinfunction "AVSS_29") (pintype "power_in"))
      (node (ref "U8") (pin "31") (pinfunction "SENSE_31") (pintype "input"))
      (node (ref "U8") (pin "33") (pinfunction "REFCOM_33") (pintype "power_in"))
      (node (ref "U9") (pin "3") (pinfunction "IN+_3") (pintype "input"))
    )
    (net (code "94") (name "DGND") (class "Default")
      (node (ref "C38") (pin "1") (pinfunction "1_1") (pintype "passive"))
      (node (ref "C39") (pin "1") (pinfunction "1_1") (pintype "passive"))
      (node (ref "C44") (pin "2") (pinfunction "2_2") (pintype "passive"))
      (node (ref "C45") (pin "2") (pinfunction "2_2") (pintype "passive"))
      (node (ref "J2") (pin "1") (pinfunction "1_1") (pintype "passive"))
      (node (ref "R28") (pin "1") (pinfunction "1_1") (pintype "passive"))
      (node (ref "U12") (pin "1") (pinfunction "GND_1") (pintype "power_in"))
      (node (ref "U12") (pin "3") (pinfunction "NC_3") (pintype "passive"))
      (node (ref "U12") (pin "4") (pinfunction "NC_4") (pintype "passive"))
      (node (ref "U12") (pin "5") (pinfunction "NC_5") (pintype "passive"))
      (node (ref "U12") (pin "6") (pinfunction "NC_6") (pintype "passive"))
      (node (ref "U5") (pin "1") (pinfunction "~{OE}_1") (pintype "input"))
      (node (ref "U5") (pin "10") (pinfunction "GND_10") (pintype "power_in"))
      (node (ref "U6") (pin "1") (pinfunction "~{OE}_1") (pintype "input"))
      (node (ref "U6") (pin "10") (pinfunction "GND_10") (pintype "power_in"))
      (node (ref "U8") (pin "1") (pinfunction "DVSS_1") (pintype "power_in"))
      (node (ref "U8") (pin "5") (pinfunction "DRVSS_5") (pintype "power_in"))
      (node (ref "VR2") (pin "1") (pinfunction "GND_1") (pintype "passive"))
    )
    (net (code "95") (name "Net-(C34-Pad1)") (class "Default")
      (node (ref "C34") (pin "1") (pinfunction "1_1") (pintype "passive"))
      (node (ref "R23") (pin "2") (pinfunction "2_2") (pintype "passive"))
      (node (ref "R24") (pin "1") (pinfunction "1_1") (pintype "passive"))
    )
    (net (code "96") (name "Net-(D1-K)") (class "Default")
      (node (ref "C34") (pin "2") (pinfunction "2_2") (pintype "passive"))
      (node (ref "D1") (pin "3") (pinfunction "K_3") (pintype "passive"))
      (node (ref "R20") (pin "1") (pinfunction "1_1") (pintype "passive"))
      (node (ref "R25") (pin "2") (pinfunction "2_2") (pintype "passive"))
      (node (ref "U9") (pin "6") (pinfunction "IN-_6") (pintype "input"))
      (node (ref "U9") (pin "7") (pinfunction "OUT_7") (pintype "output"))
    )
    (net (code "97") (name "Net-(R18-Pad1)") (class "Default")
      (node (ref "R18") (pin "1") (pinfunction "1_1") (pintype "passive"))
      (node (ref "R19") (pin "2") (pinfunction "2_2") (pintype "passive"))
    )
    (net (code "98") (name "Net-(R21-+)") (class "Default")
      (node (ref "R21") (pin "CW") (pinfunction "+_CW") (pintype "passive"))
      (node (ref "R22") (pin "2") (pinfunction "2_2") (pintype "passive"))
      (node (ref "U9") (pin "2") (pinfunction "IN-_2") (pintype "input"))
    )
    (net (code "99") (name "Net-(R21--)") (class "Default")
      (node (ref "R21") (pin "CCW") (pinfunction "-_CCW") (pintype "passive"))
      (node (ref "R21") (pin "W") (pinfunction "W_W") (pintype "passive"))
      (node (ref "R23") (pin "1") (pinfunction "1_1") (pintype "passive"))
      (node (ref "U9") (pin "1") (pinfunction "OUT_1") (pintype "output"))
    )
    (net (code "100") (name "Net-(U7-+IN)") (class "Default")
      (node (ref "C25") (pin "1") (pinfunction "1_1") (pintype "passive"))
      (node (ref "R15") (pin "1") (pinfunction "1_1") (pintype "passive"))
      (node (ref "R20") (pin "2") (pinfunction "2_2") (pintype "passive"))
      (node (ref "U7") (pin "8") (pinfunction "+IN_8") (pintype "passive"))
    )
    (net (code "101") (name "Net-(U7--IN)") (class "Default")
      (node (ref "C24") (pin "1") (pinfunction "1_1") (pintype "passive"))
      (node (ref "R14") (pin "1") (pinfunction "1_1") (pintype "passive"))
      (node (ref "R18") (pin "2") (pinfunction "2_2") (pintype "passive"))
      (node (ref "U7") (pin "1") (pinfunction "-IN_1") (pintype "passive"))
    )
    (net (code "102") (name "Net-(U7-VCOM)") (class "Default")
      (node (ref "C28") (pin "2") (pinfunction "2_2") (pintype "passive"))
      (node (ref "U7") (pin "2") (pinfunction "VCOM_2") (pintype "passive"))
      (node (ref "U8") (pin "39") (pinfunction "CML_39") (pintype "power_in"))
    )
    (net (code "103") (name "Net-(U8-BIAS)") (class "Default")
      (node (ref "R13") (pin "2") (pinfunction "2_2") (pintype "passive"))
      (node (ref "U8") (pin "35") (pinfunction "BIAS_35") (pintype "passive"))
    )
    (net (code "104") (name "Net-(U8-CAPB)") (class "Default")
      (node (ref "C27") (pin "2") (pinfunction "2_2") (pintype "passive"))
      (node (ref "C29") (pin "1") (pinfunction "1_1") (pintype "passive"))
      (node (ref "C31") (pin "1") (pinfunction "1_1") (pintype "passive"))
      (node (ref "U8") (pin "36") (pinfunction "CAPB_36") (pintype "passive"))
    )
    (net (code "105") (name "Net-(U8-CAPT)") (class "Default")
      (node (ref "C26") (pin "1") (pinfunction "1_1") (pintype "passive"))
      (node (ref "C27") (pin "1") (pinfunction "1_1") (pintype "passive"))
      (node (ref "C29") (pin "2") (pinfunction "2_2") (pintype "passive"))
      (node (ref "U8") (pin "37") (pinfunction "CAPT_37") (pintype "passive"))
    )
    (net (code "106") (name "Net-(U8-VREF)") (class "Default")
      (node (ref "C32") (pin "1") (pinfunction "1_1") (pintype "passive"))
      (node (ref "C33") (pin "2") (pinfunction "2_2") (pintype "passive"))
      (node (ref "U8") (pin "32") (pinfunction "VREF_32") (pintype "bidirectional"))
    )
    (net (code "107") (name "Net-(U9B-IN+)") (class "Default")
      (node (ref "C35") (pin "2") (pinfunction "2_2") (pintype "passive"))
      (node (ref "R24") (pin "2") (pinfunction "2_2") (pintype "passive"))
      (node (ref "U9") (pin "5") (pinfunction "IN+_5") (pintype "input"))
    )
    (net (code "108") (name "Net-(U21-ADJ)") (class "Default")
      (node (ref "R54") (pin "1") (pinfunction "1_1") (pintype "passive"))
      (node (ref "R56") (pin "2") (pinfunction "2_2") (pintype "passive"))
      (node (ref "U21") (pin "1") (pinfunction "ADJ_1") (pintype "input"))
    )
    (net (code "109") (name "VCCO") (class "Default")
      (node (ref "C45") (pin "1") (pinfunction "1_1") (pintype "passive"))
      (node (ref "R29") (pin "2") (pinfunction "2_2") (pintype "passive"))
      (node (ref "U8") (pin "6") (pinfunction "DRVDD_6") (pintype "power_in"))
      (node (ref "VR2") (pin "2") (pinfunction "Vout_2") (pintype "passive"))
    )
    (net (code "110") (name "VE") (class "Default")
      (node (ref "P10") (pin "A32") (pinfunction "A32_A32") (pintype "passive"))
      (node (ref "P10") (pin "B32") (pinfunction "B32_B32") (pintype "passive"))
      (node (ref "P10") (pin "C32") (pinfunction "C32_C32") (pintype "passive"))
    )
    (net (code "111") (name "VO") (class "Default")
      (node (ref "R22") (pin "1") (pinfunction "1_1") (pintype "passive"))
    )
    (net (code "112") (name "unconnected-(P10-PadA16)") (class "Default")
      (node (ref "P10") (pin "A16") (pinfunction "A16_A16") (pintype "passive"))
    )
    (net (code "113") (name "unconnected-(P10-PadA17)") (class "Default")
      (node (ref "P10") (pin "A17") (pinfunction "A17_A17") (pintype "passive"))
    )
    (net (code "114") (name "unconnected-(P10-PadA20)") (class "Default")
      (node (ref "P10") (pin "A20") (pinfunction "A20_A20") (pintype "passive+no_connect"))
    )
    (net (code "115") (name "unconnected-(P10-PadA21)") (class "Default")
      (node (ref "P10") (pin "A21") (pinfunction "A21_A21") (pintype "passive+no_connect"))
    )
    (net (code "116") (name "unconnected-(P10-PadA22)") (class "Default")
      (node (ref "P10") (pin "A22") (pinfunction "A22_A22") (pintype "passive+no_connect"))
    )
    (net (code "117") (name "unconnected-(P10-PadA23)") (class "Default")
      (node (ref "P10") (pin "A23") (pinfunction "A23_A23") (pintype "passive"))
    )
    (net (code "118") (name "unconnected-(P10-PadA25)") (class "Default")
      (node (ref "P10") (pin "A25") (pinfunction "A25_A25") (pintype "passive+no_connect"))
    )
    (net (code "119") (name "unconnected-(P10-PadA26)") (class "Default")
      (node (ref "P10") (pin "A26") (pinfunction "A26_A26") (pintype "passive+no_connect"))
    )
    (net (code "120") (name "unconnected-(P10-PadA27)") (class "Default")
      (node (ref "P10") (pin "A27") (pinfunction "A27_A27") (pintype "passive+no_connect"))
    )
    (net (code "121") (name "unconnected-(P10-PadA28)") (class "Default")
      (node (ref "P10") (pin "A28") (pinfunction "A28_A28") (pintype "passive+no_connect"))
    )
    (net (code "122") (name "unconnected-(P10-PadB4)") (class "Default")
      (node (ref "P10") (pin "B4") (pinfunction "B4_B4") (pintype "passive+no_connect"))
    )
    (net (code "123") (name "unconnected-(P10-PadB5)") (class "Default")
      (node (ref "P10") (pin "B5") (pinfunction "B5_B5") (pintype "passive+no_connect"))
    )
    (net (code "124") (name "unconnected-(P10-PadB6)") (class "Default")
      (node (ref "P10") (pin "B6") (pinfunction "B6_B6") (pintype "passive+no_connect"))
    )
    (net (code "125") (name "unconnected-(P10-PadB7)") (class "Default")
      (node (ref "P10") (pin "B7") (pinfunction "B7_B7") (pintype "passive+no_connect"))
    )
    (net (code "126") (name "unconnected-(P10-PadB8)") (class "Default")
      (node (ref "P10") (pin "B8") (pinfunction "B8_B8") (pintype "passive+no_connect"))
    )
    (net (code "127") (name "unconnected-(P10-PadB9)") (class "Default")
      (node (ref "P10") (pin "B9") (pinfunction "B9_B9") (pintype "passive+no_connect"))
    )
    (net (code "128") (name "unconnected-(P10-PadB10)") (class "Default")
      (node (ref "P10") (pin "B10") (pinfunction "B10_B10") (pintype "passive+no_connect"))
    )
    (net (code "129") (name "unconnected-(P10-PadB11)") (class "Default")
      (node (ref "P10") (pin "B11") (pinfunction "B11_B11") (pintype "passive+no_connect"))
    )
    (net (code "130") (name "unconnected-(P10-PadB16)") (class "Default")
      (node (ref "P10") (pin "B16") (pinfunction "B16_B16") (pintype "passive"))
    )
    (net (code "131") (name "unconnected-(P10-PadB17)") (class "Default")
      (node (ref "P10") (pin "B17") (pinfunction "B17_B17") (pintype "passive"))
    )
    (net (code "132") (name "unconnected-(P10-PadB18)") (class "Default")
      (node (ref "P10") (pin "B18") (pinfunction "B18_B18") (pintype "passive"))
    )
    (net (code "133") (name "unconnected-(P10-PadB19)") (class "Default")
      (node (ref "P10") (pin "B19") (pinfunction "B19_B19") (pintype "passive"))
    )
    (net (code "134") (name "unconnected-(P10-PadB20)") (class "Default")
      (node (ref "P10") (pin "B20") (pinfunction "B20_B20") (pintype "passive"))
    )
    (net (code "135") (name "unconnected-(P10-PadB21)") (class "Default")
      (node (ref "P10") (pin "B21") (pinfunction "B21_B21") (pintype "passive"))
    )
    (net (code "136") (name "unconnected-(P10-PadB22)") (class "Default")
      (node (ref "P10") (pin "B22") (pinfunction "B22_B22") (pintype "passive"))
    )
    (net (code "137") (name "unconnected-(P10-PadB23)") (class "Default")
      (node (ref "P10") (pin "B23") (pinfunction "B23_B23") (pintype "passive"))
    )
    (net (code "138") (name "unconnected-(P10-PadB25)") (class "Default")
      (node (ref "P10") (pin "B25") (pinfunction "B25_B25") (pintype "passive+no_connect"))
    )
    (net (code "139") (name "unconnected-(P10-PadB26)") (class "Default")
      (node (ref "P10") (pin "B26") (pinfunction "B26_B26") (pintype "passive+no_connect"))
    )
    (net (code "140") (name "unconnected-(P10-PadB27)") (class "Default")
      (node (ref "P10") (pin "B27") (pinfunction "B27_B27") (pintype "passive+no_connect"))
    )
    (net (code "141") (name "unconnected-(P10-PadB28)") (class "Default")
      (node (ref "P10") (pin "B28") (pinfunction "B28_B28") (pintype "passive+no_connect"))
    )
    (net (code "142") (name "unconnected-(P10-PadC20)") (class "Default")
      (node (ref "P10") (pin "C20") (pinfunction "C20_C20") (pintype "passive+no_connect"))
    )
    (net (code "143") (name "unconnected-(P10-PadC21)") (class "Default")
      (node (ref "P10") (pin "C21") (pinfunction "C21_C21") (pintype "passive+no_connect"))
    )
    (net (code "144") (name "unconnected-(P10-PadC22)") (class "Default")
      (node (ref "P10") (pin "C22") (pinfunction "C22_C22") (pintype "passive+no_connect"))
    )
    (net (code "145") (name "unconnected-(P10-PadC23)") (class "Default")
      (node (ref "P10") (pin "C23") (pinfunction "C23_C23") (pintype "passive"))
    )
    (net (code "146") (name "unconnected-(P10-PadC25)") (class "Default")
      (node (ref "P10") (pin "C25") (pinfunction "C25_C25") (pintype "passive+no_connect"))
    )
    (net (code "147") (name "unconnected-(P10-PadC26)") (class "Default")
      (node (ref "P10") (pin "C26") (pinfunction "C26_C26") (pintype "passive+no_connect"))
    )
    (net (code "148") (name "unconnected-(P10-PadC27)") (class "Default")
      (node (ref "P10") (pin "C27") (pinfunction "C27_C27") (pintype "passive+no_connect"))
    )
    (net (code "149") (name "unconnected-(P10-PadC28)") (class "Default")
      (node (ref "P10") (pin "C28") (pinfunction "C28_C28") (pintype "passive+no_connect"))
    )
    (net (code "150") (name "unconnected-(U7-NC-Pad7)") (class "Default")
      (node (ref "U7") (pin "7") (pinfunction "NC_7") (pintype "passive"))
    )
    (net (code "151") (name "unconnected-(U8-NC-Pad8)") (class "Default")
      (node (ref "U8") (pin "8") (pinfunction "NC_8") (pintype "passive+no_connect"))
    )
    (net (code "152") (name "unconnected-(U8-NC-Pad9)") (class "Default")
      (node (ref "U8") (pin "9") (pinfunction "NC_9") (pintype "passive+no_connect"))
    )
    (net (code "153") (name "unconnected-(U8-NC-Pad10)") (class "Default")
      (node (ref "U8") (pin "10") (pinfunction "NC_10") (pintype "passive+no_connect"))
    )
    (net (code "154") (name "unconnected-(U8-NC-Pad26)") (class "Default")
      (node (ref "U8") (pin "26") (pinfunction "NC_26") (pintype "passive+no_connect"))
    )
    (net (code "155") (name "unconnected-(U8-NC-Pad27)") (class "Default")
      (node (ref "U8") (pin "27") (pinfunction "NC_27") (pintype "passive+no_connect"))
    )
    (net (code "156") (name "unconnected-(U8-NC-Pad30)") (class "Default")
      (node (ref "U8") (pin "30") (pinfunction "NC_30") (pintype "passive+no_connect"))
    )
    (net (code "157") (name "unconnected-(U8-NC-Pad34)") (class "Default")
      (node (ref "U8") (pin "34") (pinfunction "NC_34") (pintype "passive+no_connect"))
    )
    (net (code "158") (name "unconnected-(U8-NC-Pad38)") (class "Default")
      (node (ref "U8") (pin "38") (pinfunction "NC_38") (pintype "passive+no_connect"))
    )
    (net (code "159") (name "unconnected-(U8-NC-Pad40)") (class "Default")
      (node (ref "U8") (pin "40") (pinfunction "NC_40") (pintype "passive+no_connect"))
    )
    (net (code "160") (name "unconnected-(U8-NC-Pad43)") (class "Default")
      (node (ref "U8") (pin "43") (pinfunction "NC_43") (pintype "passive+no_connect"))
    )
    (net (code "161") (name "unconnected-(U8-NC-Pad44)") (class "Default")
      (node (ref "U8") (pin "44") (pinfunction "NC_44") (pintype "passive+no_connect"))
    )
    (net (code "162") (name "unconnected-(U10-R-Pad1)") (class "Default")
      (node (ref "U10") (pin "1") (pinfunction "R_1") (pintype "passive"))
    )
    (net (code "163") (name "unconnected-(U11-R-Pad1)") (class "Default")
      (node (ref "U11") (pin "1") (pinfunction "R_1") (pintype "passive"))
    )
  )
)
